# Face_PWR1V0.net
KiCad netlist of a schematic drawn in Altium Designer
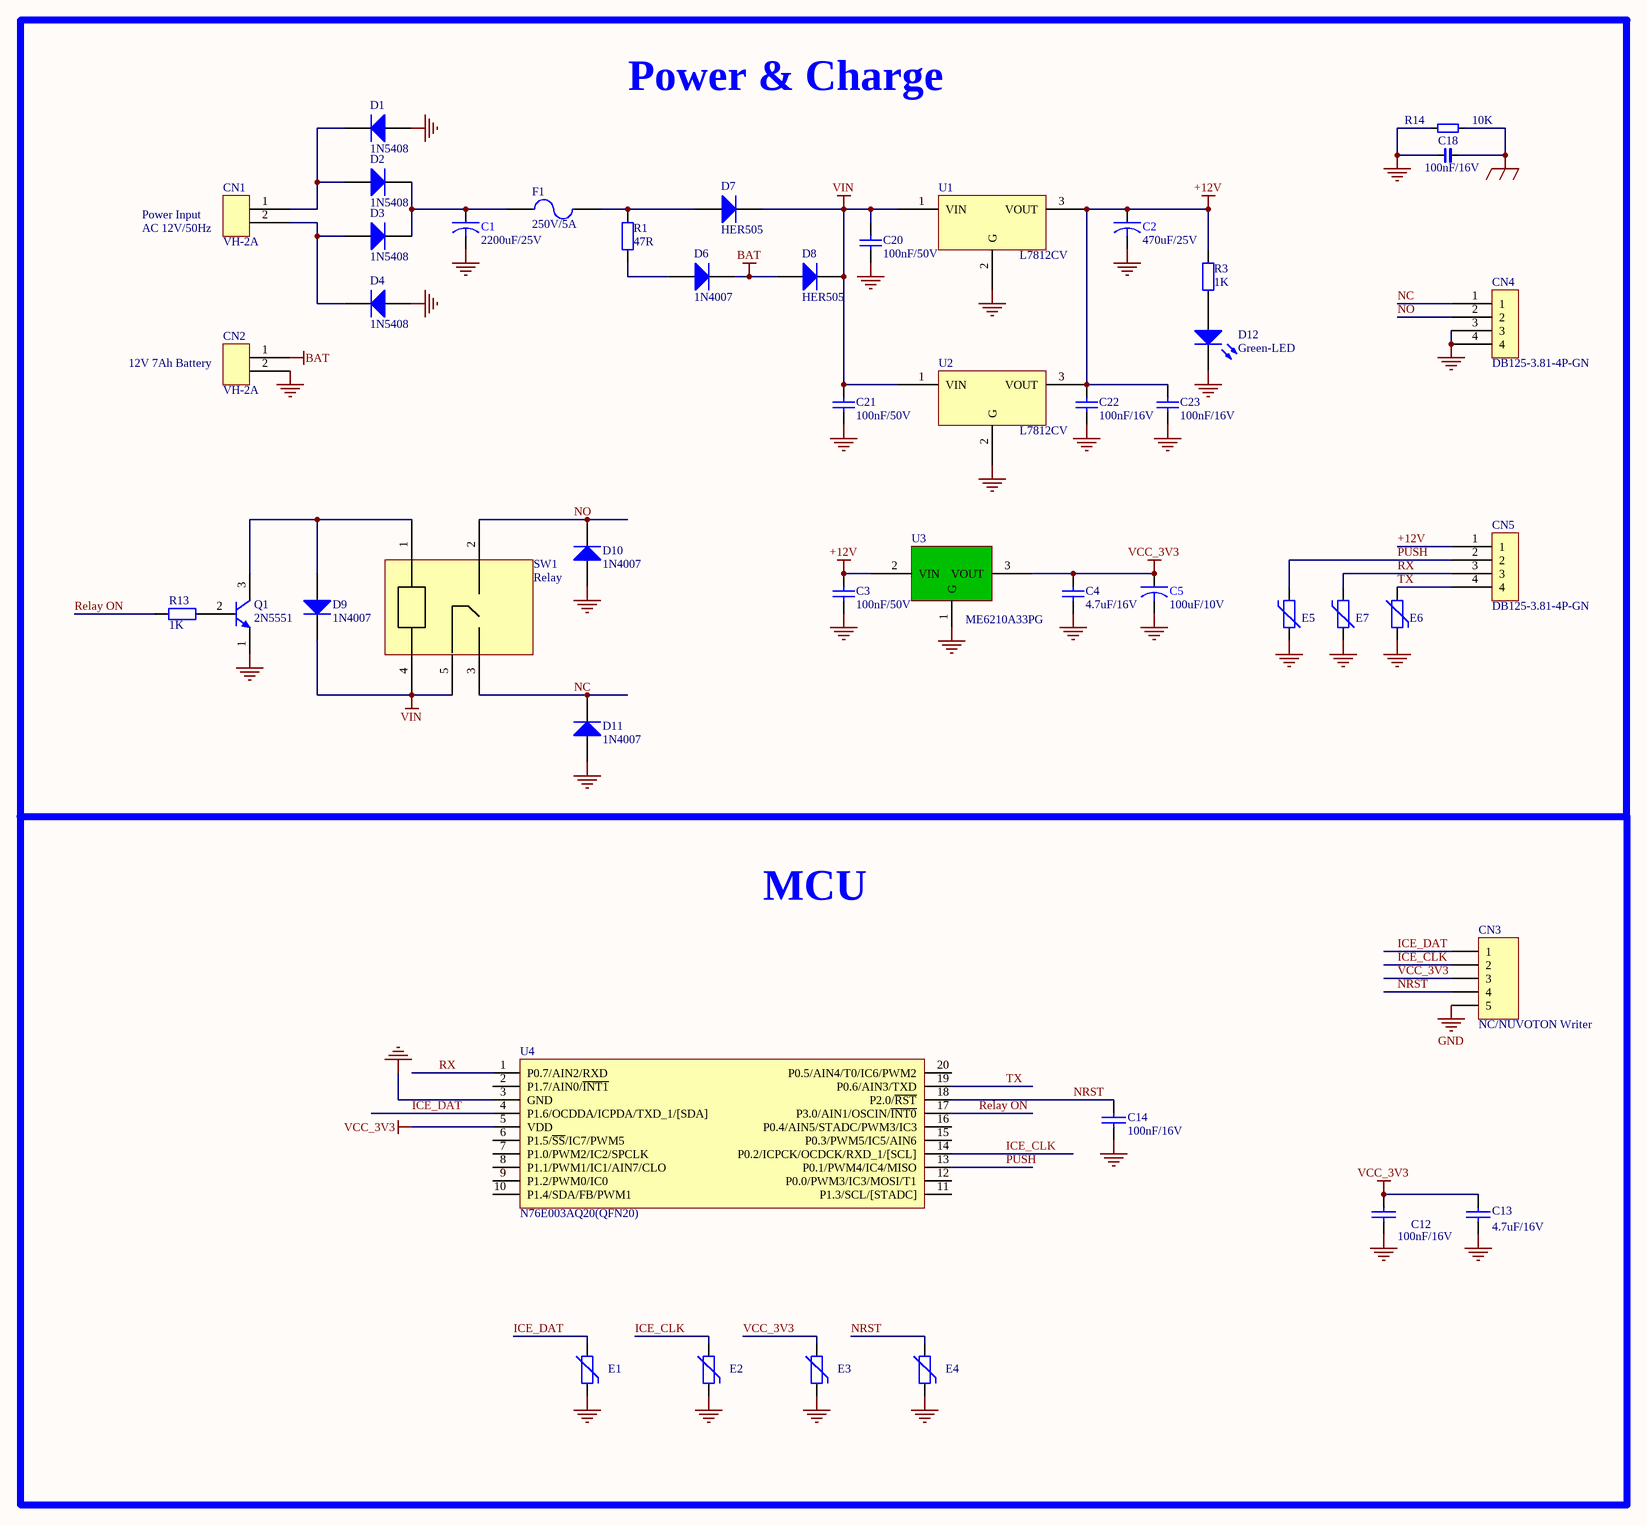
[diagram p0: Face_PWR1V0.SchDoc]

(export (version "E")
  (design (tool "Eeschema 10.0.6"))
  (components
    (comp (ref "C1")
      (value "2200uF/25V")
      (footprint "CAP 13x21mm")
      (description "2200uF 25V 13*20")
      (libsource (lib "LM") (part "CAP_Polaric"))
    )
    (comp (ref "C2")
      (value "470uF/25V")
      (footprint "CAP-TH_BD8.0-P3.50-D1.0-FD")
      (description "470uF/25V(RC025M471LO8*14TH-2A1E)")
      (libsource (lib "LM") (part "CAP_Polaric"))
    )
    (comp (ref "C3")
      (value "100nF/50V")
      (footprint "C0603")
      (description "0.1uF/50V 10%  0603 X5R ROHS")
      (fields (field (name "PUBLISHER") "Altium Limited"))
      (libsource (lib "Miscellaneous Devices") (part "Cap"))
    )
    (comp (ref "C4")
      (value "4.7uF/16V")
      (footprint "C0603")
      (description "4.7uF/16V 10% 0603 X7R ROHS")
      (fields (field (name "PUBLISHER") "Altium Limited"))
      (libsource (lib "Miscellaneous Devices") (part "Cap"))
    )
    (comp (ref "C5")
      (value "100uF/10V")
      (footprint "C_ALU_5.3MM")
      (description "CS1A101M-CRD54, 100uF/10V")
      (libsource (lib "LM") (part "CAP_Polaric"))
    )
    (comp (ref "C12")
      (value "100nF/16V")
      (footprint "C0402")
      (description "100nF/16V 10% 0402 X7R ROHS")
      (libsource (lib "S8Main2V0") (part "CAP"))
    )
    (comp (ref "C13")
      (value "4.7uF/16V")
      (footprint "C0603")
      (description "4.7uF/16V 10% 0603 X7R ROHS")
      (libsource (lib "S8Main2V0") (part "CAP"))
    )
    (comp (ref "C14")
      (value "100nF/16V")
      (footprint "C0402")
      (description "100nF/16V 10% 0402 X7R ROHS")
      (libsource (lib "S8Main2V0") (part "CAP"))
    )
    (comp (ref "C18")
      (value "100nF/16V")
      (footprint "C0402")
      (description "100nF/16V 10% 0402 X7R ROHS")
      (libsource (lib "FL01M1V5") (part "CAP"))
    )
    (comp (ref "C20")
      (value "100nF/50V")
      (footprint "C0603")
      (description "0.1uF/50V 10%  0603 X5R ROHS")
      (fields (field (name "PUBLISHER") "Altium Limited"))
      (libsource (lib "Miscellaneous Devices") (part "Cap"))
    )
    (comp (ref "C21")
      (value "100nF/50V")
      (footprint "C0603")
      (description "0.1uF/50V 10%  0603 X5R ROHS")
      (fields (field (name "PUBLISHER") "Altium Limited"))
      (libsource (lib "Miscellaneous Devices") (part "Cap"))
    )
    (comp (ref "C22")
      (value "100nF/16V")
      (footprint "C0402")
      (description "100nF ±10% 16V X7R 0402 ROHS")
      (fields (field (name "PUBLISHER") "Altium Limited"))
      (libsource (lib "Miscellaneous Devices") (part "Cap"))
    )
    (comp (ref "C23")
      (value "100nF/16V")
      (footprint "C0402")
      (description "100nF ±10% 16V X7R 0402 ROHS")
      (fields (field (name "PUBLISHER") "Altium Limited"))
      (libsource (lib "Miscellaneous Devices") (part "Cap"))
    )
    (comp (ref "CN1") (value "VH-2A") (footprint "VH3.96-2A") (libsource (lib "") (part "Component_1_1")))
    (comp (ref "CN2") (value "VH-2A") (footprint "VH3.96-2A") (libsource (lib "") (part "Component_1_1")))
    (comp (ref "CN3")
      (value "NC/NUVOTON Writer")
      (footprint "HD5_2.0")
      (description "SH1.25_5P_SMD_TOP")
      (libsource (lib "S8Main2V0") (part "Header 5"))
    )
    (comp (ref "CN4")
      (value "DB125-3.81-4P-GN")
      (footprint "DB125-3.81-4P-GN")
      (libsource (lib "") (part "Component_1_3"))
    )
    (comp (ref "CN5")
      (value "DB125-3.81-4P-GN")
      (footprint "DB125-3.81-4P-GN")
      (libsource (lib "") (part "Component_1_3"))
    )
    (comp (ref "D1")
      (value "1N5408")
      (footprint "DO-201AD")
      (description "1N5408(DO-201AD)")
      (libsource (lib "LM") (part "M2 (DO-214AC)"))
    )
    (comp (ref "D2")
      (value "1N5408")
      (footprint "DO-201AD")
      (description "1N5408(DO-201AD)")
      (libsource (lib "LM") (part "M2 (DO-214AC)"))
    )
    (comp (ref "D3")
      (value "1N5408")
      (footprint "DO-201AD")
      (description "1N5408(DO-201AD)")
      (libsource (lib "LM") (part "M2 (DO-214AC)"))
    )
    (comp (ref "D4")
      (value "1N5408")
      (footprint "DO-201AD")
      (description "1N5408(DO-201AD)")
      (libsource (lib "LM") (part "M2 (DO-214AC)"))
    )
    (comp (ref "D6")
      (value "1N4007")
      (footprint "DO-41")
      (description "1N4007(DO-41)")
      (libsource (lib "LM") (part "M2 (DO-214AC)"))
    )
    (comp (ref "D7")
      (value "HER505")
      (footprint "DO-201AD")
      (description "HER505(DO-201AD)")
      (libsource (lib "LM") (part "M2 (DO-214AC)"))
    )
    (comp (ref "D8")
      (value "HER505")
      (footprint "DO-201AD")
      (description "HER505(DO-201AD)")
      (libsource (lib "LM") (part "M2 (DO-214AC)"))
    )
    (comp (ref "D9")
      (value "1N4007")
      (footprint "DO-41")
      (description "1N4007(DO-41)")
      (libsource (lib "LM") (part "M2 (DO-214AC)"))
    )
    (comp (ref "D10")
      (value "1N4007")
      (footprint "DO-41")
      (description "1N4007(DO-41)")
      (libsource (lib "LM") (part "M2 (DO-214AC)"))
    )
    (comp (ref "D11")
      (value "1N4007")
      (footprint "DO-41")
      (description "1N4007(DO-41)")
      (libsource (lib "LM") (part "M2 (DO-214AC)"))
    )
    (comp (ref "D12")
      (value "Green-LED")
      (footprint "LED-TH_BD3.0-P2.54-FD")
      (description "TJ-L3FYTGCWMCGLFLC6B-A5")
      (fields (field (name "PUBLISHER") "Altium Limited"))
      (libsource (lib "Miscellaneous Devices") (part "LED1"))
    )
    (comp (ref "E1")
      (value "SFI0402-050E330NP-LF")
      (footprint "R0402")
      (libsource (lib "S8Main2V0") (part "VARISTOR"))
    )
    (comp (ref "E2")
      (value "SFI0402-050E330NP-LF")
      (footprint "R0402")
      (libsource (lib "S8Main2V0") (part "VARISTOR"))
    )
    (comp (ref "E3")
      (value "SFI0402-050E330NP-LF")
      (footprint "R0402")
      (libsource (lib "S8Main2V0") (part "VARISTOR"))
    )
    (comp (ref "E4")
      (value "SFI0402-050E330NP-LF")
      (footprint "R0402")
      (libsource (lib "S8Main2V0") (part "VARISTOR"))
    )
    (comp (ref "E5")
      (value "SFI0402-050E330NP-LF")
      (footprint "R0402")
      (libsource (lib "S8Main2V0") (part "VARISTOR"))
    )
    (comp (ref "E6")
      (value "SFI0402-050E330NP-LF")
      (footprint "R0402")
      (libsource (lib "S8Main2V0") (part "VARISTOR"))
    )
    (comp (ref "E7")
      (value "SFI0402-050E330NP-LF")
      (footprint "R0402")
      (libsource (lib "S8Main2V0") (part "VARISTOR"))
    )
    (comp (ref "F1")
      (value "250V/5A")
      (footprint "5x20 Fuse socket")
      (description "250V/5A(5F.5000220000R1)")
      (fields (field (name "PUBLISHER") "Altium Limited"))
      (libsource (lib "Miscellaneous Devices") (part "Fuse 2"))
    )
    (comp (ref "Q1")
      (value "2N5551")
      (footprint "TO-92-3_L4.8-W3.7-P2.54L")
      (fields (field (name "PUBLISHER") "Altium Limited"))
      (libsource (lib "Miscellaneous Devices") (part "2N3904"))
    )
    (comp (ref "R1")
      (value "47R")
      (footprint "AXIAL-1.3")
      (description "47R/6W 5%(EWWR0006J47R0T9)")
      (fields (field (name "PUBLISHER") "Altium Limited"))
      (libsource (lib "") (part "Res2_1"))
    )
    (comp (ref "R3")
      (value "1K")
      (footprint "R0603")
      (description "1K +/-5% 1/10W 0603 ROHS")
      (fields (field (name "PUBLISHER") "Altium Limited"))
      (libsource (lib "") (part "Res2_1"))
    )
    (comp (ref "R13")
      (value "1K")
      (footprint "R0402")
      (description "1K +/-5% 1/16W 0402 ROHS")
      (fields (field (name "PUBLISHER") "Altium Limited"))
      (libsource (lib "Miscellaneous Devices") (part "Res2"))
    )
    (comp (ref "R14")
      (value "10K")
      (footprint "R0402")
      (description "10K +/-5% 1/16W 0402 ROHS")
      (fields (field (name "PUBLISHER") "Altium Limited"))
      (libsource (lib "FL01M1V5") (part "RES2"))
    )
    (comp (ref "SW1")
      (value "Relay")
      (footprint "RELAY-TH_SRD-XXVDC-XL-C")
      (description "SRD-12VDC-SL-C")
      (libsource (lib "") (part "Component_1_2"))
    )
    (comp (ref "U1")
      (value "L7812CV")
      (footprint "TO-220-3")
      (libsource (lib "Schlib1") (part "Component_1"))
    )
    (comp (ref "U2")
      (value "L7812CV")
      (footprint "TO-220-3")
      (libsource (lib "Schlib1") (part "Component_1"))
    )
    (comp (ref "U3")
      (value "ME6210A33PG")
      (footprint "SOT-89")
      (description "ME6210A33PG (SOT89-3)")
      (libsource (lib "LM") (part "HT7333"))
    )
    (comp (ref "U4")
      (value "N76E003AQ20(QFN20)")
      (footprint "QFN20_3*3mm")
      (fields (field (name "ALTIUM_UNNAMED_1") "N76E003AQ20(QFN20)"))
      (libsource (lib "LM") (part "N76E003AQ20"))
    )
  )
  (nets
    (net (code "1") (name "+12V") (class "Default")
      (node (ref "C2") (pin "1") (pinfunction "1_1") (pintype "passive"))
      (node (ref "C22") (pin "2") (pinfunction "2_2") (pintype "passive"))
      (node (ref "C23") (pin "2") (pinfunction "2_2") (pintype "passive"))
      (node (ref "C3") (pin "2") (pinfunction "2_2") (pintype "passive"))
      (node (ref "CN5") (pin "1") (pinfunction "1_1") (pintype "passive"))
      (node (ref "R3") (pin "2") (pinfunction "2_2") (pintype "passive"))
      (node (ref "U1") (pin "3") (pinfunction "VOUT_3") (pintype "passive"))
      (node (ref "U2") (pin "3") (pinfunction "VOUT_3") (pintype "passive"))
      (node (ref "U3") (pin "2") (pinfunction "VIN_2") (pintype "passive"))
    )
    (net (code "2") (name "/ICE_CLK") (class "Default")
      (node (ref "CN3") (pin "2") (pinfunction "2_2") (pintype "passive"))
      (node (ref "E2") (pin "1") (pinfunction "1_1") (pintype "passive"))
      (node (ref "U4") (pin "14") (pinfunction "P0.2/ICPCK/OCDCK/RXD_1/[SCL]_14") (pintype "passive"))
    )
    (net (code "3") (name "/ICE_DAT") (class "Default")
      (node (ref "CN3") (pin "1") (pinfunction "1_1") (pintype "passive"))
      (node (ref "E1") (pin "1") (pinfunction "1_1") (pintype "passive"))
      (node (ref "U4") (pin "4") (pinfunction "P1.6/OCDDA/ICPDA/TXD_1/[SDA]_4") (pintype "passive"))
    )
    (net (code "4") (name "/NC") (class "Default")
      (node (ref "CN4") (pin "1") (pinfunction "1_1") (pintype "passive"))
      (node (ref "D11") (pin "2") (pinfunction "K_2") (pintype "passive"))
      (node (ref "SW1") (pin "3") (pinfunction "3_3") (pintype "passive"))
    )
    (net (code "5") (name "/NO") (class "Default")
      (node (ref "CN4") (pin "2") (pinfunction "2_2") (pintype "passive"))
      (node (ref "D10") (pin "2") (pinfunction "K_2") (pintype "passive"))
      (node (ref "SW1") (pin "2") (pinfunction "2_2") (pintype "passive"))
    )
    (net (code "6") (name "/NRST") (class "Default")
      (node (ref "C14") (pin "1") (pinfunction "1_1") (pintype "passive"))
      (node (ref "CN3") (pin "4") (pinfunction "4_4") (pintype "passive"))
      (node (ref "E4") (pin "1") (pinfunction "1_1") (pintype "passive"))
      (node (ref "U4") (pin "18") (pinfunction "P2.0/~{RST}_18") (pintype "passive"))
    )
    (net (code "7") (name "/PUSH") (class "Default")
      (node (ref "CN5") (pin "2") (pinfunction "2_2") (pintype "passive"))
      (node (ref "E5") (pin "2") (pinfunction "2_2") (pintype "passive"))
      (node (ref "U4") (pin "13") (pinfunction "P0.1/PWM4/IC4/MISO_13") (pintype "passive"))
    )
    (net (code "8") (name "/RX") (class "Default")
      (node (ref "CN5") (pin "3") (pinfunction "3_3") (pintype "passive"))
      (node (ref "E7") (pin "2") (pinfunction "2_2") (pintype "passive"))
      (node (ref "U4") (pin "1") (pinfunction "P0.7/AIN2/RXD_1") (pintype "passive"))
    )
    (net (code "9") (name "/Relay ON") (class "Default")
      (node (ref "R13") (pin "2") (pinfunction "2_2") (pintype "passive"))
      (node (ref "U4") (pin "17") (pinfunction "P3.0/AIN1/OSCIN/~{INT0}_17") (pintype "passive"))
    )
    (net (code "10") (name "/TX") (class "Default")
      (node (ref "CN5") (pin "4") (pinfunction "4_4") (pintype "passive"))
      (node (ref "E6") (pin "1") (pinfunction "1_1") (pintype "passive"))
      (node (ref "U4") (pin "19") (pinfunction "P0.6/AIN3/TXD_19") (pintype "passive"))
    )
    (net (code "11") (name "BAT") (class "Default")
      (node (ref "CN2") (pin "1") (pinfunction "1_1") (pintype "passive"))
      (node (ref "D6") (pin "2") (pinfunction "K_2") (pintype "passive"))
      (node (ref "D8") (pin "1") (pinfunction "A_1") (pintype "passive"))
    )
    (net (code "12") (name "BODY GND") (class "Default")
      (node (ref "C18") (pin "2") (pinfunction "2_2") (pintype "passive"))
      (node (ref "R14") (pin "2") (pinfunction "2_2") (pintype "passive"))
    )
    (net (code "13") (name "GND") (class "Default")
      (node (ref "C1") (pin "2") (pinfunction "2_2") (pintype "passive"))
      (node (ref "C12") (pin "2") (pinfunction "2_2") (pintype "passive"))
      (node (ref "C13") (pin "2") (pinfunction "2_2") (pintype "passive"))
      (node (ref "C14") (pin "2") (pinfunction "2_2") (pintype "passive"))
      (node (ref "C18") (pin "1") (pinfunction "1_1") (pintype "passive"))
      (node (ref "C2") (pin "2") (pinfunction "2_2") (pintype "passive"))
      (node (ref "C20") (pin "1") (pinfunction "1_1") (pintype "passive"))
      (node (ref "C21") (pin "1") (pinfunction "1_1") (pintype "passive"))
      (node (ref "C22") (pin "1") (pinfunction "1_1") (pintype "passive"))
      (node (ref "C23") (pin "1") (pinfunction "1_1") (pintype "passive"))
      (node (ref "C3") (pin "1") (pinfunction "1_1") (pintype "passive"))
      (node (ref "C4") (pin "1") (pinfunction "1_1") (pintype "passive"))
      (node (ref "C5") (pin "2") (pinfunction "2_2") (pintype "passive"))
      (node (ref "CN2") (pin "2") (pinfunction "2_2") (pintype "passive"))
      (node (ref "CN3") (pin "5") (pinfunction "5_5") (pintype "passive"))
      (node (ref "CN4") (pin "3") (pinfunction "3_3") (pintype "passive"))
      (node (ref "CN4") (pin "4") (pinfunction "4_4") (pintype "passive"))
      (node (ref "D1") (pin "1") (pinfunction "A_1") (pintype "passive"))
      (node (ref "D10") (pin "1") (pinfunction "A_1") (pintype "passive"))
      (node (ref "D11") (pin "1") (pinfunction "A_1") (pintype "passive"))
      (node (ref "D12") (pin "2") (pinfunction "K_2") (pintype "passive"))
      (node (ref "D4") (pin "1") (pinfunction "A_1") (pintype "passive"))
      (node (ref "E1") (pin "2") (pinfunction "2_2") (pintype "passive"))
      (node (ref "E2") (pin "2") (pinfunction "2_2") (pintype "passive"))
      (node (ref "E3") (pin "2") (pinfunction "2_2") (pintype "passive"))
      (node (ref "E4") (pin "2") (pinfunction "2_2") (pintype "passive"))
      (node (ref "E5") (pin "1") (pinfunction "1_1") (pintype "passive"))
      (node (ref "E6") (pin "2") (pinfunction "2_2") (pintype "passive"))
      (node (ref "E7") (pin "1") (pinfunction "1_1") (pintype "passive"))
      (node (ref "Q1") (pin "1") (pinfunction "E_1") (pintype "passive"))
      (node (ref "R14") (pin "1") (pinfunction "1_1") (pintype "passive"))
      (node (ref "U1") (pin "2") (pinfunction "G_2") (pintype "passive"))
      (node (ref "U2") (pin "2") (pinfunction "G_2") (pintype "passive"))
      (node (ref "U3") (pin "1") (pinfunction "G_1") (pintype "passive"))
      (node (ref "U4") (pin "3") (pinfunction "GND_3") (pintype "passive"))
    )
    (net (code "14") (name "Net-(D1-K)") (class "Default")
      (node (ref "CN1") (pin "1") (pinfunction "1_1") (pintype "passive"))
      (node (ref "D1") (pin "2") (pinfunction "K_2") (pintype "passive"))
      (node (ref "D2") (pin "1") (pinfunction "A_1") (pintype "passive"))
    )
    (net (code "15") (name "Net-(D2-K)") (class "Default")
      (node (ref "C1") (pin "1") (pinfunction "1_1") (pintype "passive"))
      (node (ref "D2") (pin "2") (pinfunction "K_2") (pintype "passive"))
      (node (ref "D3") (pin "2") (pinfunction "K_2") (pintype "passive"))
      (node (ref "F1") (pin "1") (pinfunction "1_1") (pintype "passive"))
    )
    (net (code "16") (name "Net-(D3-A)") (class "Default")
      (node (ref "CN1") (pin "2") (pinfunction "2_2") (pintype "passive"))
      (node (ref "D3") (pin "1") (pinfunction "A_1") (pintype "passive"))
      (node (ref "D4") (pin "2") (pinfunction "K_2") (pintype "passive"))
    )
    (net (code "17") (name "Net-(D6-A)") (class "Default")
      (node (ref "D6") (pin "1") (pinfunction "A_1") (pintype "passive"))
      (node (ref "R1") (pin "1") (pinfunction "1_1") (pintype "passive"))
    )
    (net (code "18") (name "Net-(D7-A)") (class "Default")
      (node (ref "D7") (pin "1") (pinfunction "A_1") (pintype "passive"))
      (node (ref "F1") (pin "2") (pinfunction "2_2") (pintype "passive"))
      (node (ref "R1") (pin "2") (pinfunction "2_2") (pintype "passive"))
    )
    (net (code "19") (name "Net-(D9-A)") (class "Default")
      (node (ref "D9") (pin "1") (pinfunction "A_1") (pintype "passive"))
      (node (ref "Q1") (pin "3") (pinfunction "C_3") (pintype "passive"))
      (node (ref "SW1") (pin "1") (pinfunction "1_1") (pintype "passive"))
    )
    (net (code "20") (name "Net-(D12-A)") (class "Default")
      (node (ref "D12") (pin "1") (pinfunction "A_1") (pintype "passive"))
      (node (ref "R3") (pin "1") (pinfunction "1_1") (pintype "passive"))
    )
    (net (code "21") (name "Net-(Q1-B)") (class "Default")
      (node (ref "Q1") (pin "2") (pinfunction "B_2") (pintype "passive"))
      (node (ref "R13") (pin "1") (pinfunction "1_1") (pintype "passive"))
    )
    (net (code "22") (name "VCC_3V3") (class "Default")
      (node (ref "C12") (pin "1") (pinfunction "1_1") (pintype "passive"))
      (node (ref "C13") (pin "1") (pinfunction "1_1") (pintype "passive"))
      (node (ref "C4") (pin "2") (pinfunction "2_2") (pintype "passive"))
      (node (ref "C5") (pin "1") (pinfunction "1_1") (pintype "passive"))
      (node (ref "CN3") (pin "3") (pinfunction "3_3") (pintype "passive"))
      (node (ref "E3") (pin "1") (pinfunction "1_1") (pintype "passive"))
      (node (ref "U3") (pin "3") (pinfunction "VOUT_3") (pintype "passive"))
      (node (ref "U4") (pin "5") (pinfunction "VDD_5") (pintype "passive"))
    )
    (net (code "23") (name "VIN") (class "Default")
      (node (ref "C20") (pin "2") (pinfunction "2_2") (pintype "passive"))
      (node (ref "C21") (pin "2") (pinfunction "2_2") (pintype "passive"))
      (node (ref "D7") (pin "2") (pinfunction "K_2") (pintype "passive"))
      (node (ref "D8") (pin "2") (pinfunction "K_2") (pintype "passive"))
      (node (ref "D9") (pin "2") (pinfunction "K_2") (pintype "passive"))
      (node (ref "SW1") (pin "4") (pinfunction "4_4") (pintype "passive"))
      (node (ref "SW1") (pin "5") (pinfunction "5_5") (pintype "passive"))
      (node (ref "U1") (pin "1") (pinfunction "VIN_1") (pintype "passive"))
      (node (ref "U2") (pin "1") (pinfunction "VIN_1") (pintype "passive"))
    )
    (net (code "24") (name "unconnected-(U4-P0.0{slash}PWM3{slash}IC3{slash}MOSI{slash}T1-Pad12)") (class "Default")
      (node (ref "U4") (pin "12") (pinfunction "P0.0/PWM3/IC3/MOSI/T1_12") (pintype "passive"))
    )
    (net (code "25") (name "unconnected-(U4-P0.3{slash}PWM5{slash}IC5{slash}AIN6-Pad15)") (class "Default")
      (node (ref "U4") (pin "15") (pinfunction "P0.3/PWM5/IC5/AIN6_15") (pintype "passive"))
    )
    (net (code "26") (name "unconnected-(U4-P0.4{slash}AIN5{slash}STADC{slash}PWM3{slash}IC3-Pad16)") (class "Default")
      (node (ref "U4") (pin "16") (pinfunction "P0.4/AIN5/STADC/PWM3/IC3_16") (pintype "passive"))
    )
    (net (code "27") (name "unconnected-(U4-P0.5{slash}AIN4{slash}T0{slash}IC6{slash}PWM2-Pad20)") (class "Default")
      (node (ref "U4") (pin "20") (pinfunction "P0.5/AIN4/T0/IC6/PWM2_20") (pintype "passive"))
    )
    (net (code "28") (name "unconnected-(U4-P1.0{slash}PWM2{slash}IC2{slash}SPCLK-Pad7)") (class "Default")
      (node (ref "U4") (pin "7") (pinfunction "P1.0/PWM2/IC2/SPCLK_7") (pintype "passive"))
    )
    (net (code "29") (name "unconnected-(U4-P1.1{slash}PWM1{slash}IC1{slash}AIN7{slash}CLO-Pad8)") (class "Default")
      (node (ref "U4") (pin "8") (pinfunction "P1.1/PWM1/IC1/AIN7/CLO_8") (pintype "passive"))
    )
    (net (code "30") (name "unconnected-(U4-P1.2{slash}PWM0{slash}IC0-Pad9)") (class "Default")
      (node (ref "U4") (pin "9") (pinfunction "P1.2/PWM0/IC0_9") (pintype "passive"))
    )
    (net (code "31") (name "unconnected-(U4-P1.3{slash}SCL{slash}[STADC]-Pad11)") (class "Default")
      (node (ref "U4") (pin "11") (pinfunction "P1.3/SCL/[STADC]_11") (pintype "passive"))
    )
    (net (code "32") (name "unconnected-(U4-P1.4{slash}SDA{slash}FB{slash}PWM1-Pad10)") (class "Default")
      (node (ref "U4") (pin "10") (pinfunction "P1.4/SDA/FB/PWM1_10") (pintype "passive"))
    )
    (net (code "33") (name "unconnected-(U4-P1.5{slash}~{SS}{slash}IC7{slash}PWM5-Pad6)") (class "Default")
      (node (ref "U4") (pin "6") (pinfunction "P1.5/~{SS}/IC7/PWM5_6") (pintype "passive"))
    )
    (net (code "34") (name "unconnected-(U4-P1.7{slash}AIN0{slash}~{INT1}-Pad2)") (class "Default")
      (node (ref "U4") (pin "2") (pinfunction "P1.7/AIN0/~{INT1}_2") (pintype "passive"))
    )
  )
)
